# flatsat-breakout-aux.net
KiCad netlist of a schematic drawn in EAGLE
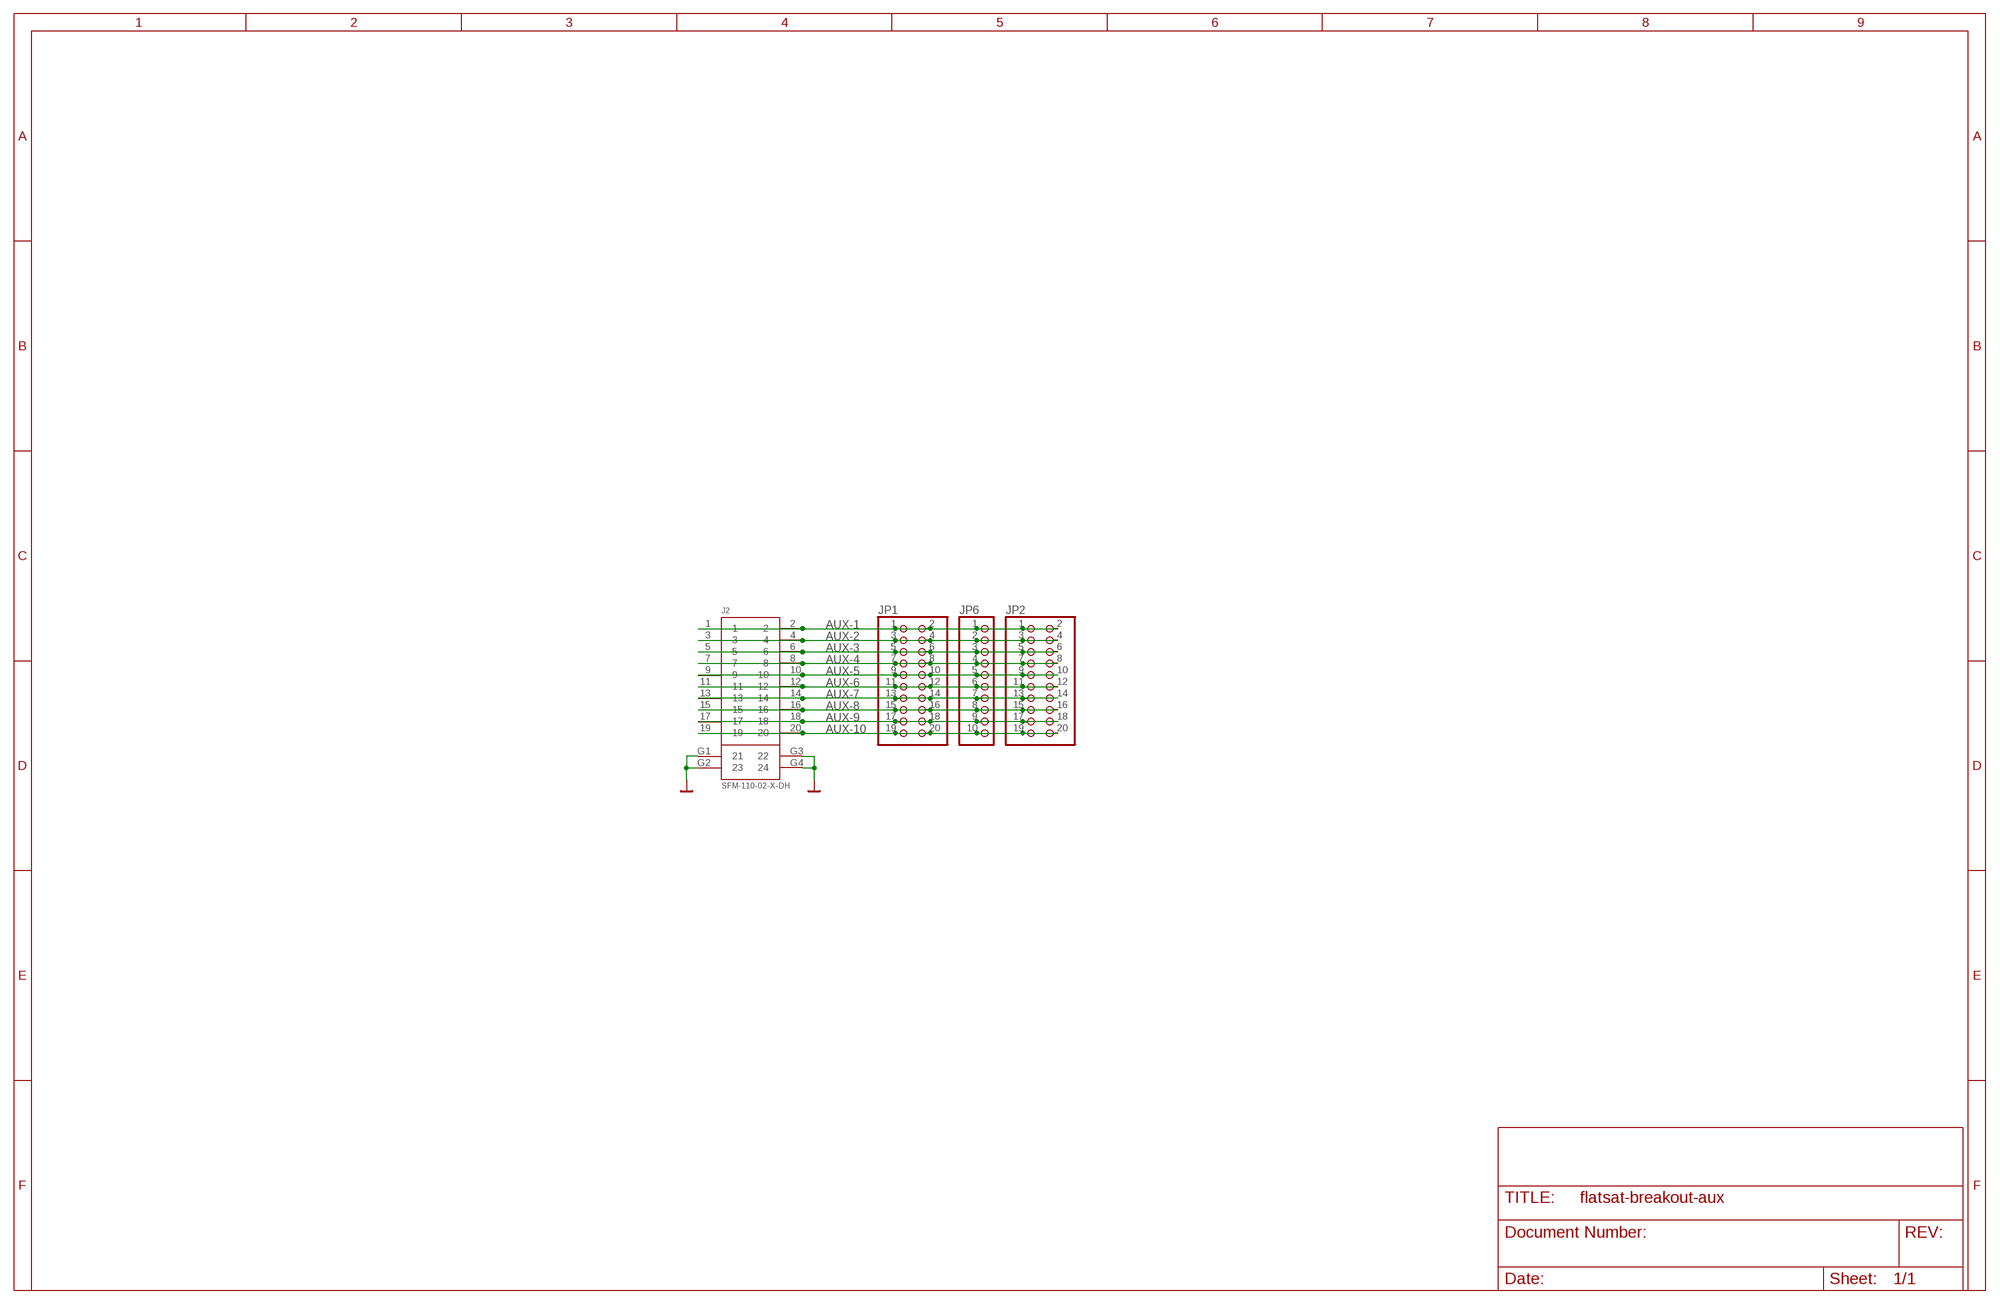
[diagram p0: schematic, sheet 1]

(export (version "E")
  (design (tool "Eeschema 10.0.6"))
  (components
    (comp (ref "J2")
      (value "SFM-110-02-X-DH")
      (footprint "eagle-import:SFM-110-02-X-DH")
      (libsource (lib "eagle-import") (part "SFM-110-02-X-DH"))
    )
    (comp (ref "JP1")
      (value "PINHD-2X10")
      (footprint "eagle-import:2X10")
      (libsource (lib "eagle-import") (part "PINHD-2X10"))
    )
    (comp (ref "JP2")
      (value "PINHD-2X10")
      (footprint "eagle-import:2X10")
      (libsource (lib "eagle-import") (part "PINHD-2X10"))
    )
    (comp (ref "JP6")
      (value "PINHD-1X10")
      (footprint "eagle-import:1X10")
      (libsource (lib "eagle-import") (part "PINHD-1X10"))
    )
  )
  (nets
    (net (code "1") (name "/AUX-1") (class "Default")
      (node (ref "J2") (pin "1") (pinfunction "1_1") (pintype "bidirectional"))
      (node (ref "J2") (pin "2") (pinfunction "2_2") (pintype "bidirectional"))
      (node (ref "JP1") (pin "1") (pinfunction "1_1") (pintype "passive"))
      (node (ref "JP1") (pin "2") (pinfunction "2_2") (pintype "passive"))
      (node (ref "JP2") (pin "1") (pinfunction "1_1") (pintype "passive"))
      (node (ref "JP2") (pin "2") (pinfunction "2_2") (pintype "passive"))
      (node (ref "JP6") (pin "1") (pinfunction "1_1") (pintype "passive"))
    )
    (net (code "2") (name "/AUX-2") (class "Default")
      (node (ref "J2") (pin "3") (pinfunction "3_3") (pintype "bidirectional"))
      (node (ref "J2") (pin "4") (pinfunction "4_4") (pintype "bidirectional"))
      (node (ref "JP1") (pin "3") (pinfunction "3_3") (pintype "passive"))
      (node (ref "JP1") (pin "4") (pinfunction "4_4") (pintype "passive"))
      (node (ref "JP2") (pin "3") (pinfunction "3_3") (pintype "passive"))
      (node (ref "JP2") (pin "4") (pinfunction "4_4") (pintype "passive"))
      (node (ref "JP6") (pin "2") (pinfunction "2_2") (pintype "passive"))
    )
    (net (code "3") (name "/AUX-3") (class "Default")
      (node (ref "J2") (pin "5") (pinfunction "5_5") (pintype "bidirectional"))
      (node (ref "J2") (pin "6") (pinfunction "6_6") (pintype "bidirectional"))
      (node (ref "JP1") (pin "5") (pinfunction "5_5") (pintype "passive"))
      (node (ref "JP1") (pin "6") (pinfunction "6_6") (pintype "passive"))
      (node (ref "JP2") (pin "5") (pinfunction "5_5") (pintype "passive"))
      (node (ref "JP2") (pin "6") (pinfunction "6_6") (pintype "passive"))
      (node (ref "JP6") (pin "3") (pinfunction "3_3") (pintype "passive"))
    )
    (net (code "4") (name "/AUX-4") (class "Default")
      (node (ref "J2") (pin "7") (pinfunction "7_7") (pintype "bidirectional"))
      (node (ref "J2") (pin "8") (pinfunction "8_8") (pintype "bidirectional"))
      (node (ref "JP1") (pin "7") (pinfunction "7_7") (pintype "passive"))
      (node (ref "JP1") (pin "8") (pinfunction "8_8") (pintype "passive"))
      (node (ref "JP2") (pin "7") (pinfunction "7_7") (pintype "passive"))
      (node (ref "JP2") (pin "8") (pinfunction "8_8") (pintype "passive"))
      (node (ref "JP6") (pin "4") (pinfunction "4_4") (pintype "passive"))
    )
    (net (code "5") (name "/AUX-5") (class "Default")
      (node (ref "J2") (pin "10") (pinfunction "10_10") (pintype "bidirectional"))
      (node (ref "J2") (pin "9") (pinfunction "9_9") (pintype "bidirectional"))
      (node (ref "JP1") (pin "10") (pinfunction "10_10") (pintype "passive"))
      (node (ref "JP1") (pin "9") (pinfunction "9_9") (pintype "passive"))
      (node (ref "JP2") (pin "10") (pinfunction "10_10") (pintype "passive"))
      (node (ref "JP2") (pin "9") (pinfunction "9_9") (pintype "passive"))
      (node (ref "JP6") (pin "5") (pinfunction "5_5") (pintype "passive"))
    )
    (net (code "6") (name "/AUX-6") (class "Default")
      (node (ref "J2") (pin "11") (pinfunction "11_11") (pintype "bidirectional"))
      (node (ref "J2") (pin "12") (pinfunction "12_12") (pintype "bidirectional"))
      (node (ref "JP1") (pin "11") (pinfunction "11_11") (pintype "passive"))
      (node (ref "JP1") (pin "12") (pinfunction "12_12") (pintype "passive"))
      (node (ref "JP2") (pin "11") (pinfunction "11_11") (pintype "passive"))
      (node (ref "JP2") (pin "12") (pinfunction "12_12") (pintype "passive"))
      (node (ref "JP6") (pin "6") (pinfunction "6_6") (pintype "passive"))
    )
    (net (code "7") (name "/AUX-7") (class "Default")
      (node (ref "J2") (pin "13") (pinfunction "13_13") (pintype "bidirectional"))
      (node (ref "J2") (pin "14") (pinfunction "14_14") (pintype "bidirectional"))
      (node (ref "JP1") (pin "13") (pinfunction "13_13") (pintype "passive"))
      (node (ref "JP1") (pin "14") (pinfunction "14_14") (pintype "passive"))
      (node (ref "JP2") (pin "13") (pinfunction "13_13") (pintype "passive"))
      (node (ref "JP2") (pin "14") (pinfunction "14_14") (pintype "passive"))
      (node (ref "JP6") (pin "7") (pinfunction "7_7") (pintype "passive"))
    )
    (net (code "8") (name "/AUX-8") (class "Default")
      (node (ref "J2") (pin "15") (pinfunction "15_15") (pintype "bidirectional"))
      (node (ref "J2") (pin "16") (pinfunction "16_16") (pintype "bidirectional"))
      (node (ref "JP1") (pin "15") (pinfunction "15_15") (pintype "passive"))
      (node (ref "JP1") (pin "16") (pinfunction "16_16") (pintype "passive"))
      (node (ref "JP2") (pin "15") (pinfunction "15_15") (pintype "passive"))
      (node (ref "JP2") (pin "16") (pinfunction "16_16") (pintype "passive"))
      (node (ref "JP6") (pin "8") (pinfunction "8_8") (pintype "passive"))
    )
    (net (code "9") (name "/AUX-9") (class "Default")
      (node (ref "J2") (pin "17") (pinfunction "17_17") (pintype "bidirectional"))
      (node (ref "J2") (pin "18") (pinfunction "18_18") (pintype "bidirectional"))
      (node (ref "JP1") (pin "17") (pinfunction "17_17") (pintype "passive"))
      (node (ref "JP1") (pin "18") (pinfunction "18_18") (pintype "passive"))
      (node (ref "JP2") (pin "17") (pinfunction "17_17") (pintype "passive"))
      (node (ref "JP2") (pin "18") (pinfunction "18_18") (pintype "passive"))
      (node (ref "JP6") (pin "9") (pinfunction "9_9") (pintype "passive"))
    )
    (net (code "10") (name "/AUX-10") (class "Default")
      (node (ref "J2") (pin "19") (pinfunction "19_19") (pintype "bidirectional"))
      (node (ref "J2") (pin "20") (pinfunction "20_20") (pintype "bidirectional"))
      (node (ref "JP1") (pin "19") (pinfunction "19_19") (pintype "passive"))
      (node (ref "JP1") (pin "20") (pinfunction "20_20") (pintype "passive"))
      (node (ref "JP2") (pin "19") (pinfunction "19_19") (pintype "passive"))
      (node (ref "JP2") (pin "20") (pinfunction "20_20") (pintype "passive"))
      (node (ref "JP6") (pin "10") (pinfunction "10_10") (pintype "passive"))
    )
    (net (code "11") (name "GND") (class "Default")
      (node (ref "J2") (pin "G1") (pinfunction "21_G1") (pintype "bidirectional"))
      (node (ref "J2") (pin "G2") (pinfunction "23_G2") (pintype "bidirectional"))
      (node (ref "J2") (pin "G3") (pinfunction "22_G3") (pintype "bidirectional"))
      (node (ref "J2") (pin "G4") (pinfunction "24_G4") (pintype "bidirectional"))
    )
  )
)
